# MRCS-Telephone-Connector.net
KiCad netlist of a schematic drawn in EAGLE
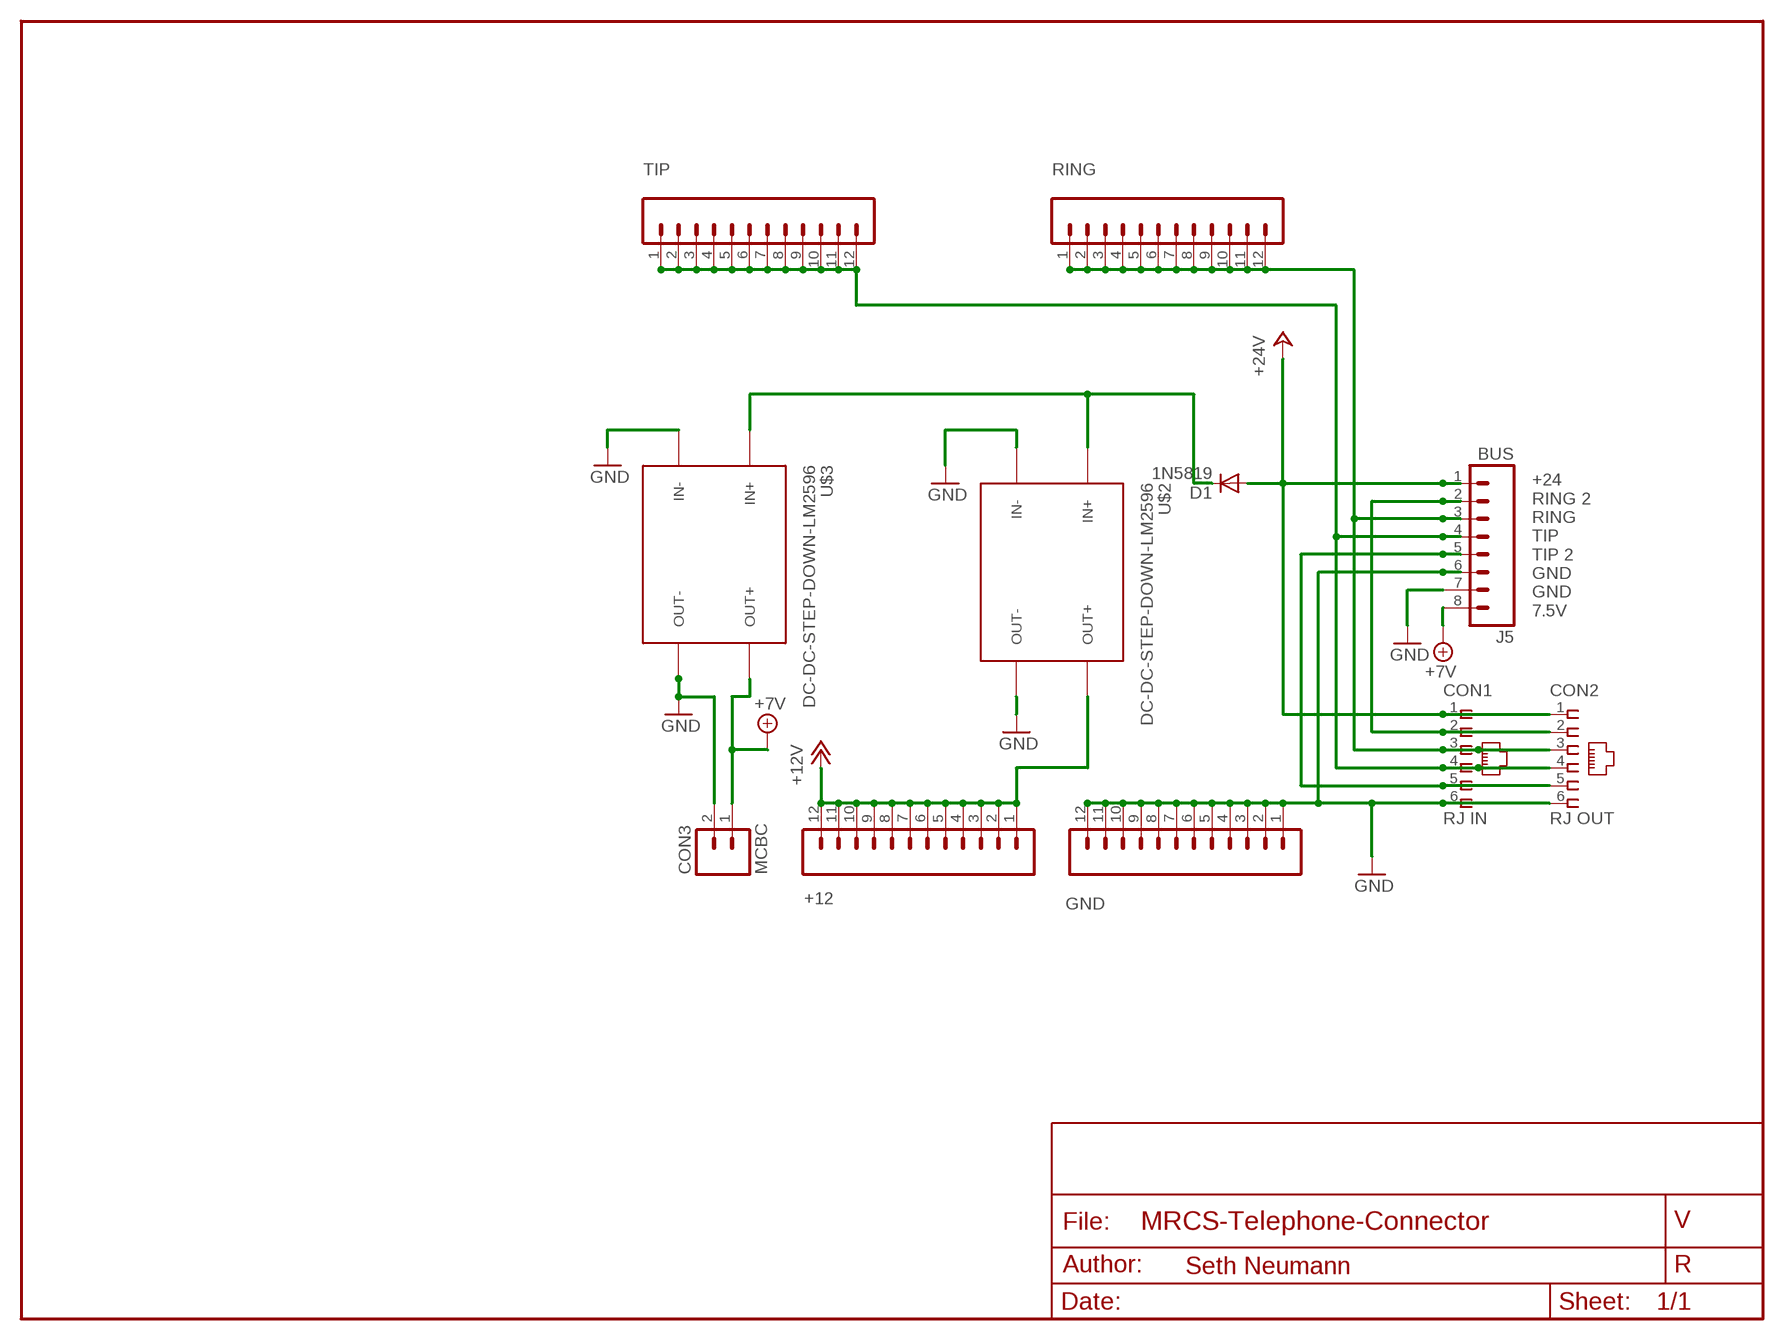
[diagram p0: schematic, sheet 1]

(export (version "E")
  (design (tool "Eeschema 10.0.6"))
  (components
    (comp (ref "+12")
      (value "CONNECTOR-M12LOCK")
      (footprint "eagle-import:1X12_LOCK")
      (libsource (lib "eagle-import") (part "CONNECTOR-M12LOCK"))
    )
    (comp (ref "CON1")
      (value "RJ IN")
      (footprint "eagle-import:RJ25-INVERTED")
      (libsource (lib "eagle-import") (part "CONNECTOR-RJ25-43860-2-MOLEX"))
    )
    (comp (ref "CON2")
      (value "RJ OUT")
      (footprint "eagle-import:RJ25-INVERTED")
      (libsource (lib "eagle-import") (part "CONNECTOR-RJ25-43860-2-MOLEX"))
    )
    (comp (ref "CON3")
      (value "MCBC")
      (footprint "eagle-import:1X02-2MM")
      (libsource (lib "eagle-import") (part "CONNECTOR-M022MM"))
    )
    (comp (ref "D1")
      (value "1N5819")
      (footprint "eagle-import:DIODE-1N4001")
      (libsource (lib "eagle-import") (part "DIODEPTH"))
    )
    (comp (ref "GND")
      (value "CONNECTOR-M12LOCK")
      (footprint "eagle-import:1X12_LOCK")
      (libsource (lib "eagle-import") (part "CONNECTOR-M12LOCK"))
    )
    (comp (ref "J5")
      (value "BUS")
      (footprint "eagle-import:1X08_LOCK")
      (libsource (lib "eagle-import") (part "CONNECTOR-M08LOCK"))
    )
    (comp (ref "RING")
      (value "CONNECTOR-M12LOCK")
      (footprint "eagle-import:1X12_LOCK")
      (libsource (lib "eagle-import") (part "CONNECTOR-M12LOCK"))
    )
    (comp (ref "TIP")
      (value "CONNECTOR-M12LOCK")
      (footprint "eagle-import:1X12_LOCK")
      (libsource (lib "eagle-import") (part "CONNECTOR-M12LOCK"))
    )
    (comp (ref "U$2")
      (value "DC-DC-STEP-DOWN-LM2596")
      (footprint "eagle-import:DC-DC-STEP-DOWN-LM2596")
      (libsource (lib "eagle-import") (part "DC-DC-STEP-DOWN-LM2596"))
    )
    (comp (ref "U$3")
      (value "DC-DC-STEP-DOWN-LM2596")
      (footprint "eagle-import:DC-DC-STEP-DOWN-LM2596")
      (libsource (lib "eagle-import") (part "DC-DC-STEP-DOWN-LM2596"))
    )
  )
  (nets
    (net (code "1") (name "+7V") (class "Default")
      (node (ref "CON3") (pin "1") (pinfunction "A_1") (pintype "passive"))
      (node (ref "J5") (pin "8") (pinfunction "8_8") (pintype "passive"))
      (node (ref "U$3") (pin "OUT+") (pinfunction "OUT+_OUT+") (pintype "bidirectional"))
    )
    (net (code "2") (name "+12V") (class "Default")
      (node (ref "+12") (pin "1") (pinfunction "1_1") (pintype "passive"))
      (node (ref "+12") (pin "10") (pinfunction "10_10") (pintype "passive"))
      (node (ref "+12") (pin "11") (pinfunction "11_11") (pintype "passive"))
      (node (ref "+12") (pin "12") (pinfunction "12_12") (pintype "passive"))
      (node (ref "+12") (pin "2") (pinfunction "2_2") (pintype "passive"))
      (node (ref "+12") (pin "3") (pinfunction "3_3") (pintype "passive"))
      (node (ref "+12") (pin "4") (pinfunction "4_4") (pintype "passive"))
      (node (ref "+12") (pin "5") (pinfunction "5_5") (pintype "passive"))
      (node (ref "+12") (pin "6") (pinfunction "6_6") (pintype "passive"))
      (node (ref "+12") (pin "7") (pinfunction "7_7") (pintype "passive"))
      (node (ref "+12") (pin "8") (pinfunction "8_8") (pintype "passive"))
      (node (ref "+12") (pin "9") (pinfunction "9_9") (pintype "passive"))
      (node (ref "U$2") (pin "OUT+") (pinfunction "OUT+_OUT+") (pintype "bidirectional"))
    )
    (net (code "3") (name "+24V") (class "Default")
      (node (ref "CON1") (pin "1") (pinfunction "1_1") (pintype "passive"))
      (node (ref "CON2") (pin "1") (pinfunction "1_1") (pintype "passive"))
      (node (ref "D1") (pin "A") (pinfunction "A_A") (pintype "passive"))
      (node (ref "J5") (pin "1") (pinfunction "1_1") (pintype "passive"))
    )
    (net (code "4") (name "GND") (class "Default")
      (node (ref "CON1") (pin "6") (pinfunction "6_6") (pintype "passive"))
      (node (ref "CON2") (pin "6") (pinfunction "6_6") (pintype "passive"))
      (node (ref "CON3") (pin "2") (pinfunction "B_2") (pintype "passive"))
      (node (ref "GND") (pin "1") (pinfunction "1_1") (pintype "passive"))
      (node (ref "GND") (pin "10") (pinfunction "10_10") (pintype "passive"))
      (node (ref "GND") (pin "11") (pinfunction "11_11") (pintype "passive"))
      (node (ref "GND") (pin "12") (pinfunction "12_12") (pintype "passive"))
      (node (ref "GND") (pin "2") (pinfunction "2_2") (pintype "passive"))
      (node (ref "GND") (pin "3") (pinfunction "3_3") (pintype "passive"))
      (node (ref "GND") (pin "4") (pinfunction "4_4") (pintype "passive"))
      (node (ref "GND") (pin "5") (pinfunction "5_5") (pintype "passive"))
      (node (ref "GND") (pin "6") (pinfunction "6_6") (pintype "passive"))
      (node (ref "GND") (pin "7") (pinfunction "7_7") (pintype "passive"))
      (node (ref "GND") (pin "8") (pinfunction "8_8") (pintype "passive"))
      (node (ref "GND") (pin "9") (pinfunction "9_9") (pintype "passive"))
      (node (ref "J5") (pin "6") (pinfunction "6_6") (pintype "passive"))
      (node (ref "J5") (pin "7") (pinfunction "7_7") (pintype "passive"))
      (node (ref "U$2") (pin "IN-") (pinfunction "IN-_IN-") (pintype "bidirectional"))
      (node (ref "U$2") (pin "OUT-") (pinfunction "OUT-_OUT-") (pintype "bidirectional"))
      (node (ref "U$3") (pin "IN-") (pinfunction "IN-_IN-") (pintype "bidirectional"))
      (node (ref "U$3") (pin "OUT-") (pinfunction "OUT-_OUT-") (pintype "bidirectional"))
    )
    (net (code "5") (name "Net-(CON1-Pad2)") (class "Default")
      (node (ref "CON1") (pin "2") (pinfunction "2_2") (pintype "passive"))
      (node (ref "CON2") (pin "2") (pinfunction "2_2") (pintype "passive"))
      (node (ref "J5") (pin "2") (pinfunction "2_2") (pintype "passive"))
    )
    (net (code "6") (name "Net-(CON1-Pad3)") (class "Default")
      (node (ref "CON1") (pin "3") (pinfunction "3_3") (pintype "passive"))
      (node (ref "CON2") (pin "3") (pinfunction "3_3") (pintype "passive"))
      (node (ref "J5") (pin "3") (pinfunction "3_3") (pintype "passive"))
      (node (ref "RING") (pin "1") (pinfunction "1_1") (pintype "passive"))
      (node (ref "RING") (pin "10") (pinfunction "10_10") (pintype "passive"))
      (node (ref "RING") (pin "11") (pinfunction "11_11") (pintype "passive"))
      (node (ref "RING") (pin "12") (pinfunction "12_12") (pintype "passive"))
      (node (ref "RING") (pin "2") (pinfunction "2_2") (pintype "passive"))
      (node (ref "RING") (pin "3") (pinfunction "3_3") (pintype "passive"))
      (node (ref "RING") (pin "4") (pinfunction "4_4") (pintype "passive"))
      (node (ref "RING") (pin "5") (pinfunction "5_5") (pintype "passive"))
      (node (ref "RING") (pin "6") (pinfunction "6_6") (pintype "passive"))
      (node (ref "RING") (pin "7") (pinfunction "7_7") (pintype "passive"))
      (node (ref "RING") (pin "8") (pinfunction "8_8") (pintype "passive"))
      (node (ref "RING") (pin "9") (pinfunction "9_9") (pintype "passive"))
    )
    (net (code "7") (name "Net-(CON1-Pad4)") (class "Default")
      (node (ref "CON1") (pin "4") (pinfunction "4_4") (pintype "passive"))
      (node (ref "CON2") (pin "4") (pinfunction "4_4") (pintype "passive"))
      (node (ref "J5") (pin "4") (pinfunction "4_4") (pintype "passive"))
      (node (ref "TIP") (pin "1") (pinfunction "1_1") (pintype "passive"))
      (node (ref "TIP") (pin "10") (pinfunction "10_10") (pintype "passive"))
      (node (ref "TIP") (pin "11") (pinfunction "11_11") (pintype "passive"))
      (node (ref "TIP") (pin "12") (pinfunction "12_12") (pintype "passive"))
      (node (ref "TIP") (pin "2") (pinfunction "2_2") (pintype "passive"))
      (node (ref "TIP") (pin "3") (pinfunction "3_3") (pintype "passive"))
      (node (ref "TIP") (pin "4") (pinfunction "4_4") (pintype "passive"))
      (node (ref "TIP") (pin "5") (pinfunction "5_5") (pintype "passive"))
      (node (ref "TIP") (pin "6") (pinfunction "6_6") (pintype "passive"))
      (node (ref "TIP") (pin "7") (pinfunction "7_7") (pintype "passive"))
      (node (ref "TIP") (pin "8") (pinfunction "8_8") (pintype "passive"))
      (node (ref "TIP") (pin "9") (pinfunction "9_9") (pintype "passive"))
    )
    (net (code "8") (name "Net-(CON1-Pad5)") (class "Default")
      (node (ref "CON1") (pin "5") (pinfunction "5_5") (pintype "passive"))
      (node (ref "CON2") (pin "5") (pinfunction "5_5") (pintype "passive"))
      (node (ref "J5") (pin "5") (pinfunction "5_5") (pintype "passive"))
    )
    (net (code "9") (name "Net-(D1-PadC)") (class "Default")
      (node (ref "D1") (pin "C") (pinfunction "C_C") (pintype "passive"))
      (node (ref "U$2") (pin "IN+") (pinfunction "IN+_IN+") (pintype "bidirectional"))
      (node (ref "U$3") (pin "IN+") (pinfunction "IN+_IN+") (pintype "bidirectional"))
    )
  )
)
